# 6coils.net
KiCad netlist of a schematic drawn in EasyEDA
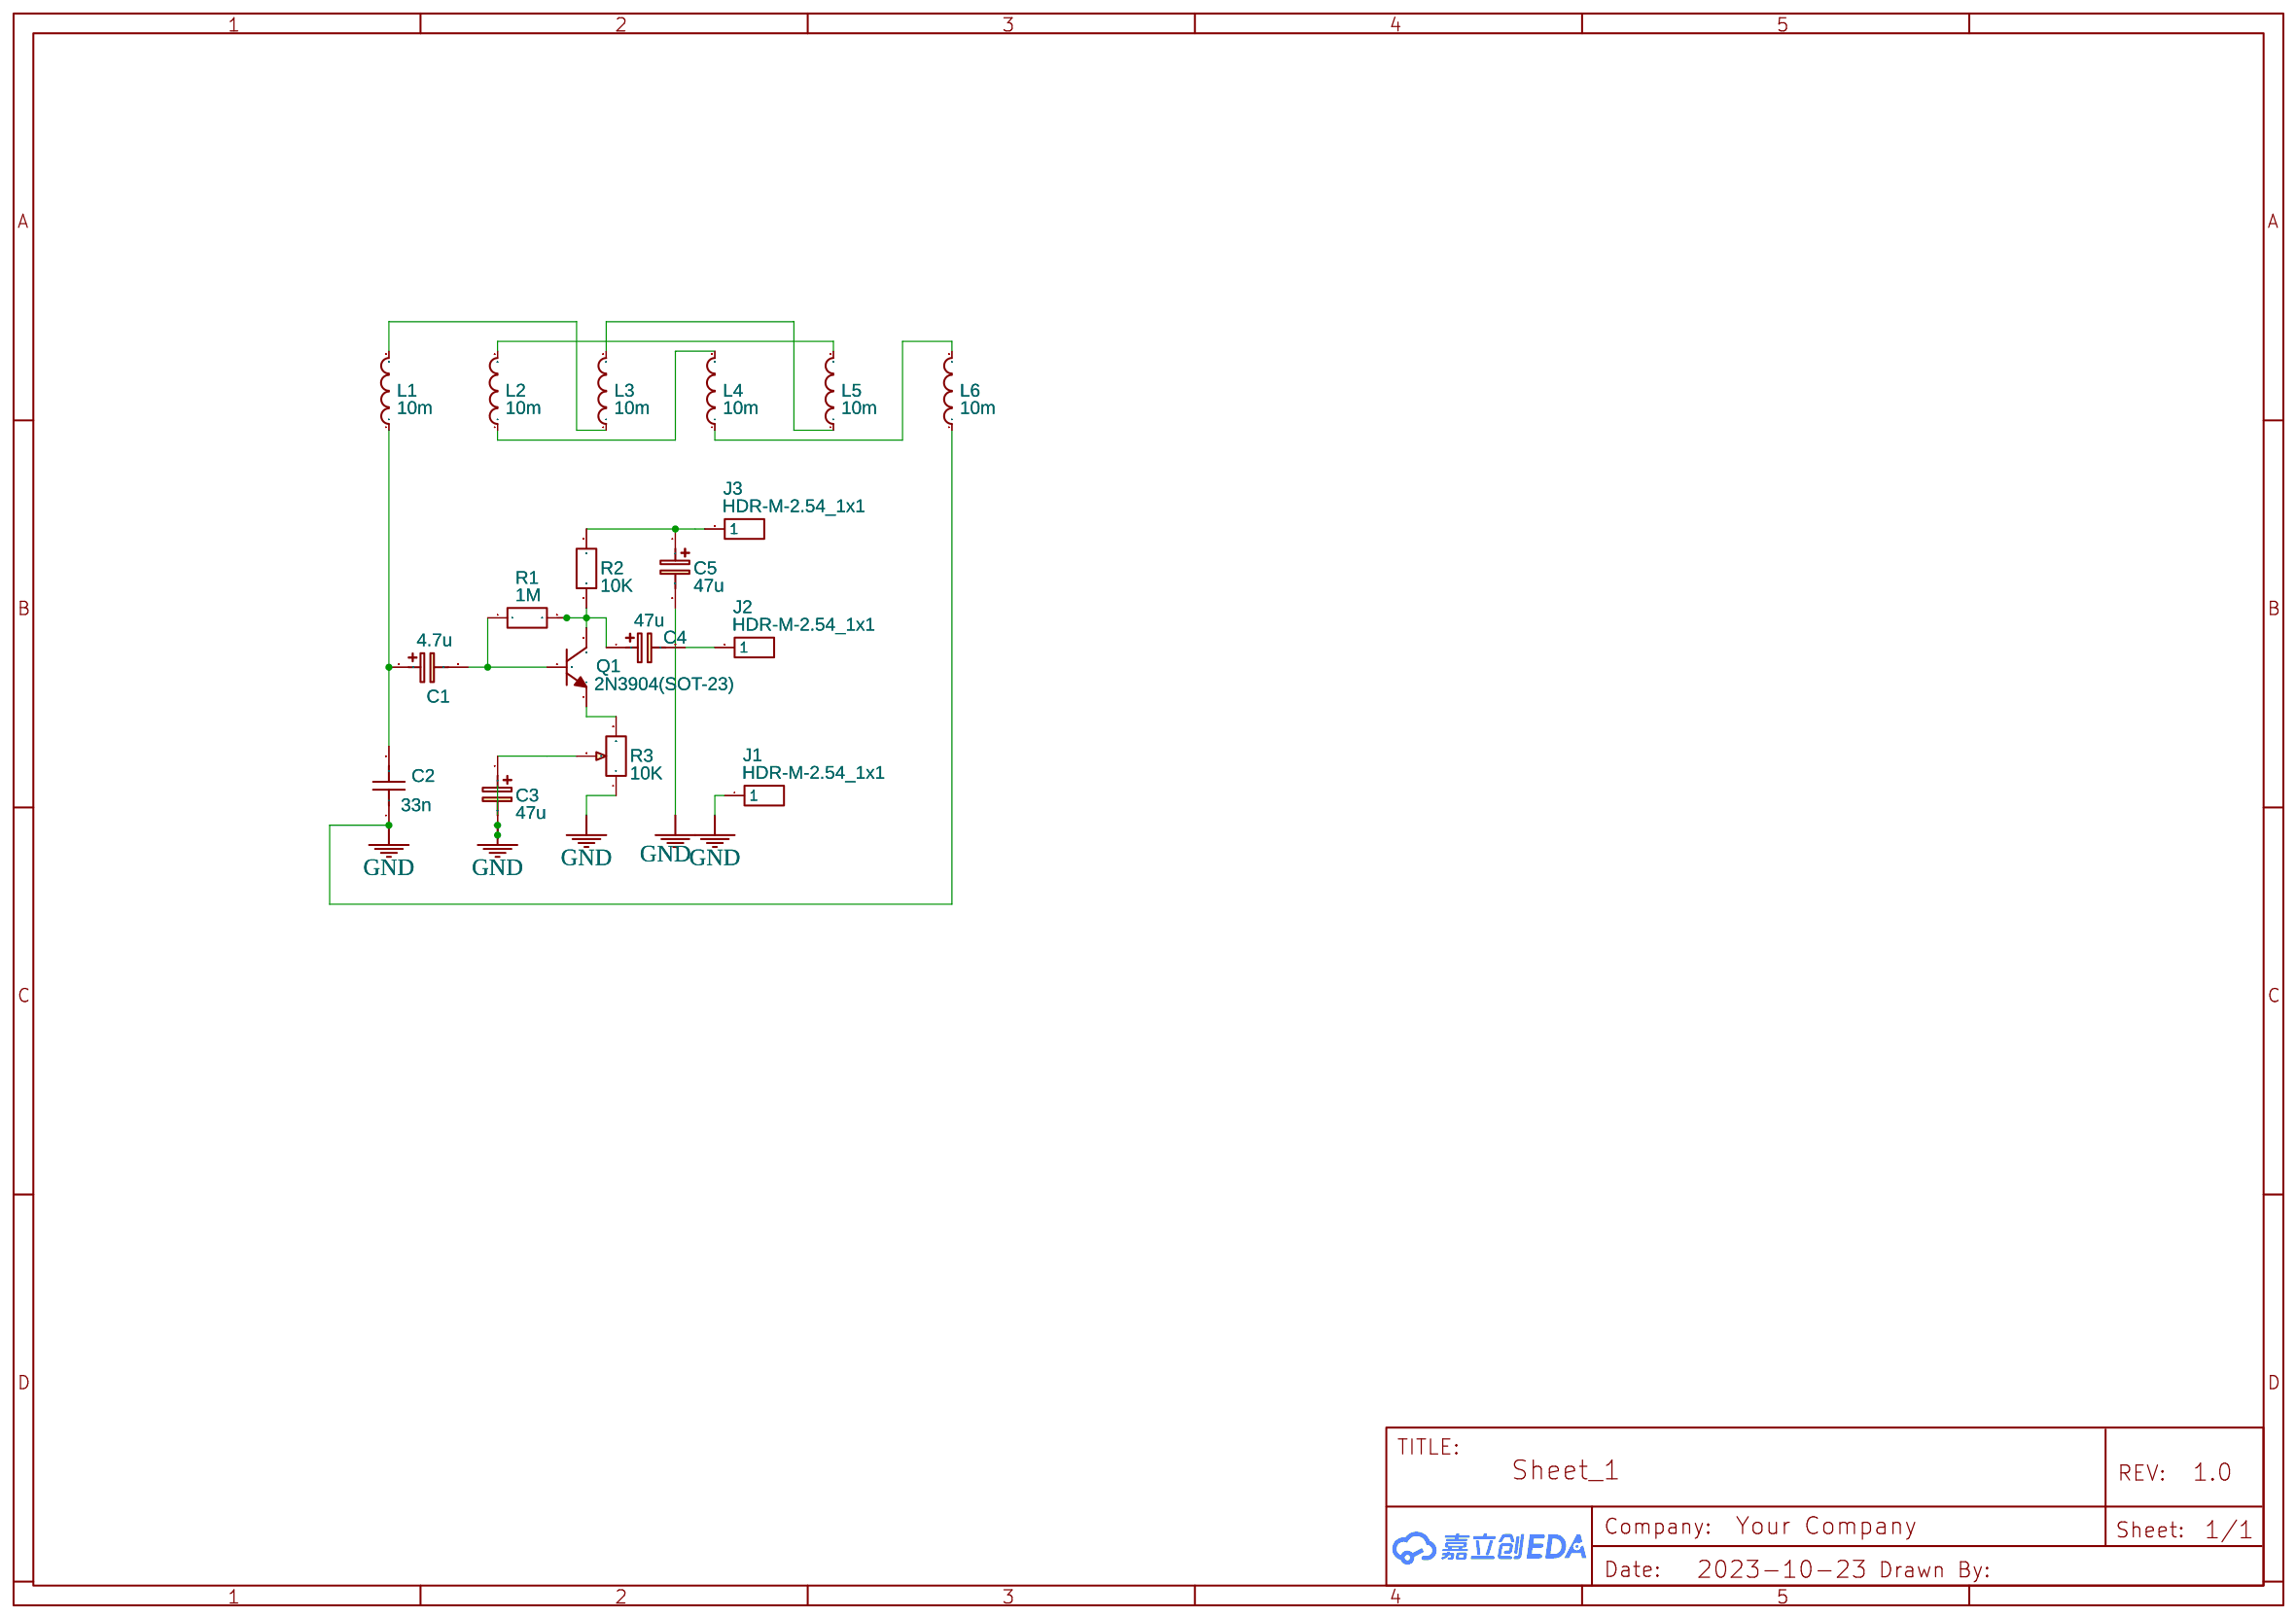
[diagram p0: schematic sheet]

(export (version "E")
  (design (tool "Eeschema 10.0.6"))
  (components
    (comp (ref "C1") (value "4.7u") (libsource (lib "") (part "C_Tan_SMD_A_EU_1")))
    (comp (ref "C2") (value "33n") (libsource (lib "") (part "C_0603_US")))
    (comp (ref "C3") (value "47u") (libsource (lib "") (part "C_Tan_SMD_A_EU")))
    (comp (ref "C4") (value "47u") (libsource (lib "") (part "C_Tan_SMD_A_EU_2")))
    (comp (ref "C5") (value "47u") (libsource (lib "") (part "C_Tan_SMD_A_EU_3")))
    (comp (ref "J1")
      (value "HDR-M-2.54_1x1")
      (fields (field (name "BOM_Supplier Part") "C81276"))
      (libsource (lib "") (part "HDR-M-2.54_1x1"))
    )
    (comp (ref "J2")
      (value "HDR-M-2.54_1x1")
      (fields (field (name "BOM_Supplier Part") "C81276"))
      (libsource (lib "") (part "HDR-M-2.54_1x1"))
    )
    (comp (ref "J3")
      (value "HDR-M-2.54_1x1")
      (fields (field (name "BOM_Supplier Part") "C81276"))
      (libsource (lib "") (part "HDR-M-2.54_1x1"))
    )
    (comp (ref "L1") (value "10m") (libsource (lib "") (part "L0603_US")))
    (comp (ref "L2") (value "10m") (libsource (lib "") (part "L0603_US")))
    (comp (ref "L3") (value "10m") (libsource (lib "") (part "L0603_US")))
    (comp (ref "L4") (value "10m") (libsource (lib "") (part "L0603_US")))
    (comp (ref "L5") (value "10m") (libsource (lib "") (part "L0603_US")))
    (comp (ref "L6") (value "10m") (libsource (lib "") (part "L0603_US")))
    (comp (ref "Q1")
      (value "2N3904(SOT-23)")
      (fields
        (field (name "BOM_Manufacturer Part") "2n3904S-RTK/PS")
        (field (name "BOM_Supplier Part") "C18536")
      )
      (libsource (lib "") (part "2N3904(SOT-23)"))
    )
    (comp (ref "R1") (value "1M") (libsource (lib "") (part "R_0603_EU")))
    (comp (ref "R2") (value "10K") (libsource (lib "") (part "R_0603_EU_1")))
    (comp (ref "R3")
      (value "10K")
      (fields (field (name "Manufacturer Part") "RM063-103 10K") (field (name "Manufacturer") "JML"))
      (libsource (lib "") (part "RM063-103 10K"))
    )
  )
  (nets
    (net (code "1") (name "GND") (class "Default")
      (node (ref "C2") (pin "1") (pinfunction "1_1") (pintype "unspecified"))
      (node (ref "C3") (pin "2") (pinfunction "2_2") (pintype "unspecified"))
      (node (ref "C5") (pin "2") (pinfunction "2_2") (pintype "unspecified"))
      (node (ref "J1") (pin "1") (pinfunction "1_1") (pintype "input"))
      (node (ref "L6") (pin "1") (pinfunction "1_1") (pintype "unspecified"))
      (node (ref "R3") (pin "1") (pinfunction "1_1") (pintype "input"))
    )
    (net (code "2") (name "Net-(C1-Pad1)") (class "Default")
      (node (ref "C1") (pin "1") (pinfunction "1_1") (pintype "unspecified"))
      (node (ref "C2") (pin "2") (pinfunction "2_2") (pintype "unspecified"))
      (node (ref "L1") (pin "1") (pinfunction "1_1") (pintype "unspecified"))
    )
    (net (code "3") (name "Net-(C3-Pad1)") (class "Default")
      (node (ref "C3") (pin "1") (pinfunction "1_1") (pintype "unspecified"))
      (node (ref "R3") (pin "2") (pinfunction "2_2") (pintype "input"))
    )
    (net (code "4") (name "Net-(C4-Pad2)") (class "Default")
      (node (ref "C4") (pin "2") (pinfunction "2_2") (pintype "unspecified"))
      (node (ref "J2") (pin "1") (pinfunction "1_1") (pintype "input"))
    )
    (net (code "5") (name "Net-(C5-Pad1)") (class "Default")
      (node (ref "C5") (pin "1") (pinfunction "1_1") (pintype "unspecified"))
      (node (ref "J3") (pin "1") (pinfunction "1_1") (pintype "input"))
      (node (ref "R2") (pin "2") (pinfunction "2_2") (pintype "unspecified"))
    )
    (net (code "6") (name "Net-(L1-Pad2)") (class "Default")
      (node (ref "L1") (pin "2") (pinfunction "2_2") (pintype "unspecified"))
      (node (ref "L3") (pin "1") (pinfunction "1_1") (pintype "unspecified"))
    )
    (net (code "7") (name "Net-(L2-Pad1)") (class "Default")
      (node (ref "L2") (pin "1") (pinfunction "1_1") (pintype "unspecified"))
      (node (ref "L4") (pin "2") (pinfunction "2_2") (pintype "unspecified"))
    )
    (net (code "8") (name "Net-(L2-Pad2)") (class "Default")
      (node (ref "L2") (pin "2") (pinfunction "2_2") (pintype "unspecified"))
      (node (ref "L5") (pin "2") (pinfunction "2_2") (pintype "unspecified"))
    )
    (net (code "9") (name "Net-(L3-Pad2)") (class "Default")
      (node (ref "L3") (pin "2") (pinfunction "2_2") (pintype "unspecified"))
      (node (ref "L5") (pin "1") (pinfunction "1_1") (pintype "unspecified"))
    )
    (net (code "10") (name "Net-(L4-Pad1)") (class "Default")
      (node (ref "L4") (pin "1") (pinfunction "1_1") (pintype "unspecified"))
      (node (ref "L6") (pin "2") (pinfunction "2_2") (pintype "unspecified"))
    )
    (net (code "11") (name "Net-(Q1-B)") (class "Default")
      (node (ref "C1") (pin "2") (pinfunction "2_2") (pintype "unspecified"))
      (node (ref "Q1") (pin "2") (pinfunction "B_2") (pintype "input"))
      (node (ref "R1") (pin "1") (pinfunction "1_1") (pintype "unspecified"))
    )
    (net (code "12") (name "Net-(Q1-C)") (class "Default")
      (node (ref "C4") (pin "1") (pinfunction "1_1") (pintype "unspecified"))
      (node (ref "Q1") (pin "3") (pinfunction "C_3") (pintype "input"))
      (node (ref "R1") (pin "2") (pinfunction "2_2") (pintype "unspecified"))
      (node (ref "R2") (pin "1") (pinfunction "1_1") (pintype "unspecified"))
    )
    (net (code "13") (name "Net-(Q1-E)") (class "Default")
      (node (ref "Q1") (pin "1") (pinfunction "E_1") (pintype "input"))
      (node (ref "R3") (pin "3") (pinfunction "3_3") (pintype "input"))
    )
  )
)
